# Noise_Percussion_main.net
KiCad netlist of a schematic drawn in EAGLE
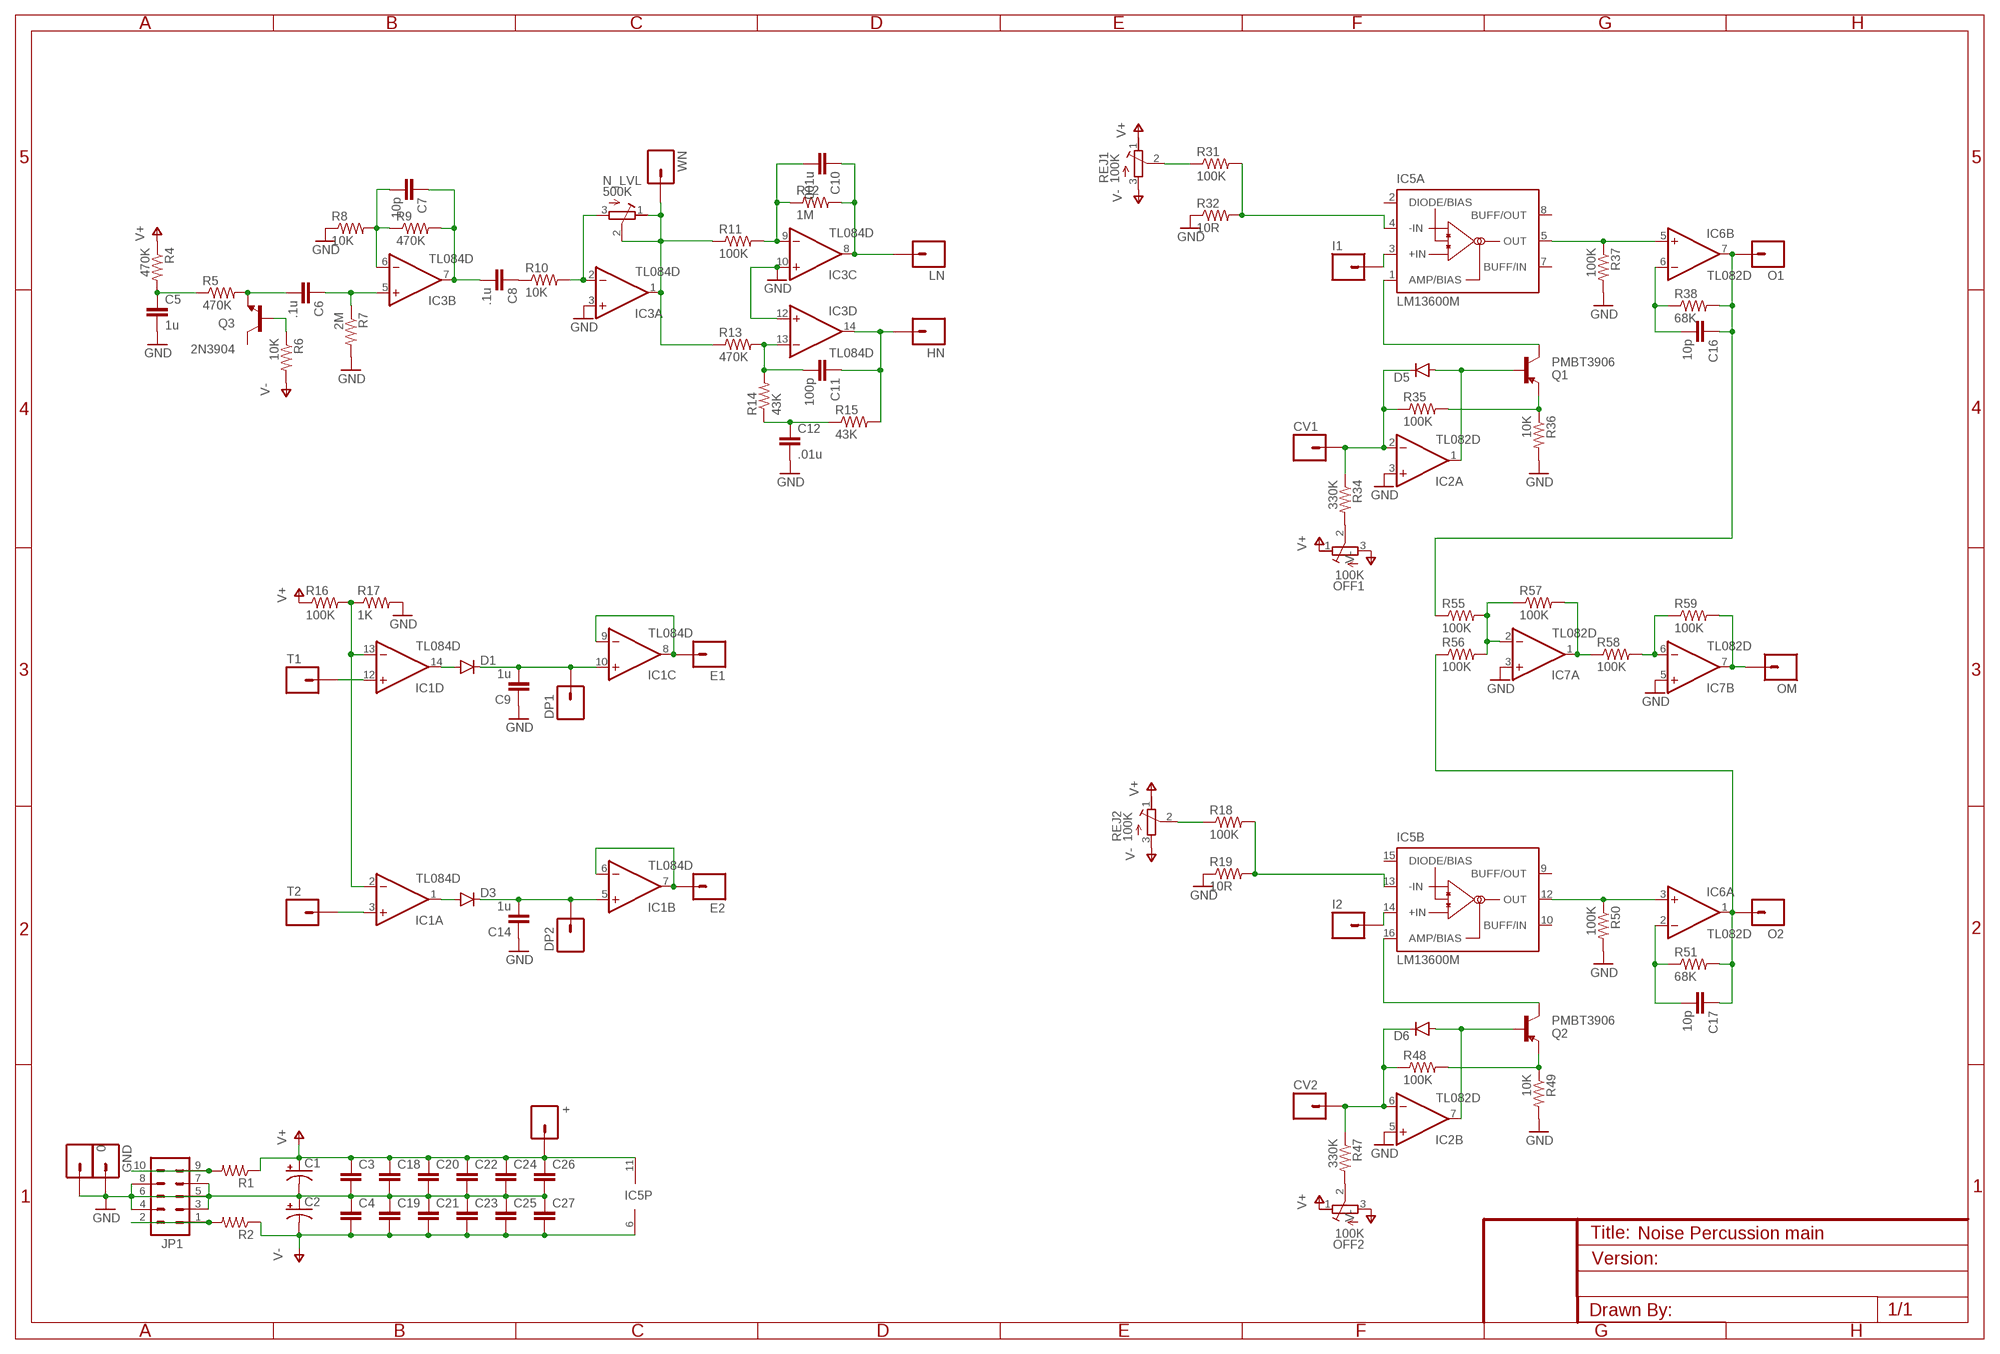
[diagram p0: schematic, sheet 1]

(export (version "E")
  (design (tool "Eeschema 10.0.6"))
  (components
    (comp (ref "+")
      (value "M01PTH")
      (footprint "eagle-import:1X01")
      (libsource (lib "eagle-import") (part "M01PTH"))
    )
    (comp (ref "0")
      (value "M01PTH")
      (footprint "eagle-import:1X01")
      (libsource (lib "eagle-import") (part "M01PTH"))
    )
    (comp (ref "C1")
      (value "CAP_POLC")
      (footprint "eagle-import:PANASONIC_C")
      (libsource (lib "eagle-import") (part "CAP_POLC"))
    )
    (comp (ref "C2")
      (value "CAP_POLC")
      (footprint "eagle-import:PANASONIC_C")
      (libsource (lib "eagle-import") (part "CAP_POLC"))
    )
    (comp (ref "C3")
      (value "CAP0805")
      (footprint "eagle-import:0805")
      (libsource (lib "eagle-import") (part "CAP0805"))
    )
    (comp (ref "C4")
      (value "CAP0805")
      (footprint "eagle-import:0805")
      (libsource (lib "eagle-import") (part "CAP0805"))
    )
    (comp (ref "C5")
      (value "1u")
      (footprint "eagle-import:0805")
      (libsource (lib "eagle-import") (part "CAP0805"))
    )
    (comp (ref "C6")
      (value ".1u")
      (footprint "eagle-import:0805")
      (libsource (lib "eagle-import") (part "CAP0805"))
    )
    (comp (ref "C7")
      (value "10p")
      (footprint "eagle-import:0805")
      (libsource (lib "eagle-import") (part "CAP0805"))
    )
    (comp (ref "C8")
      (value ".1u")
      (footprint "eagle-import:0805")
      (libsource (lib "eagle-import") (part "CAP0805"))
    )
    (comp (ref "C9")
      (value "1u")
      (footprint "eagle-import:0805")
      (libsource (lib "eagle-import") (part "CAP0805"))
    )
    (comp (ref "C10")
      (value ".001u")
      (footprint "eagle-import:0805")
      (libsource (lib "eagle-import") (part "CAP0805"))
    )
    (comp (ref "C11")
      (value "100p")
      (footprint "eagle-import:0805")
      (libsource (lib "eagle-import") (part "CAP0805"))
    )
    (comp (ref "C12")
      (value ".01u")
      (footprint "eagle-import:0805")
      (libsource (lib "eagle-import") (part "CAP0805"))
    )
    (comp (ref "C14")
      (value "1u")
      (footprint "eagle-import:0805")
      (libsource (lib "eagle-import") (part "CAP0805"))
    )
    (comp (ref "C16")
      (value "10p")
      (footprint "eagle-import:0805")
      (libsource (lib "eagle-import") (part "CAP0805"))
    )
    (comp (ref "C17")
      (value "10p")
      (footprint "eagle-import:0805")
      (libsource (lib "eagle-import") (part "CAP0805"))
    )
    (comp (ref "C18")
      (value "CAP0805")
      (footprint "eagle-import:0805")
      (libsource (lib "eagle-import") (part "CAP0805"))
    )
    (comp (ref "C19")
      (value "CAP0805")
      (footprint "eagle-import:0805")
      (libsource (lib "eagle-import") (part "CAP0805"))
    )
    (comp (ref "C20")
      (value "CAP0805")
      (footprint "eagle-import:0805")
      (libsource (lib "eagle-import") (part "CAP0805"))
    )
    (comp (ref "C21")
      (value "CAP0805")
      (footprint "eagle-import:0805")
      (libsource (lib "eagle-import") (part "CAP0805"))
    )
    (comp (ref "C22")
      (value "CAP0805")
      (footprint "eagle-import:0805")
      (libsource (lib "eagle-import") (part "CAP0805"))
    )
    (comp (ref "C23")
      (value "CAP0805")
      (footprint "eagle-import:0805")
      (libsource (lib "eagle-import") (part "CAP0805"))
    )
    (comp (ref "C24")
      (value "CAP0805")
      (footprint "eagle-import:0805")
      (libsource (lib "eagle-import") (part "CAP0805"))
    )
    (comp (ref "C25")
      (value "CAP0805")
      (footprint "eagle-import:0805")
      (libsource (lib "eagle-import") (part "CAP0805"))
    )
    (comp (ref "C26")
      (value "CAP0805")
      (footprint "eagle-import:0805")
      (libsource (lib "eagle-import") (part "CAP0805"))
    )
    (comp (ref "C27")
      (value "CAP0805")
      (footprint "eagle-import:0805")
      (libsource (lib "eagle-import") (part "CAP0805"))
    )
    (comp (ref "CV1")
      (value "M01PTH")
      (footprint "eagle-import:1X01")
      (libsource (lib "eagle-import") (part "M01PTH"))
    )
    (comp (ref "CV2")
      (value "M01PTH")
      (footprint "eagle-import:1X01")
      (libsource (lib "eagle-import") (part "M01PTH"))
    )
    (comp (ref "D1")
      (value "DIODESOD123")
      (footprint "eagle-import:SOD-123")
      (libsource (lib "eagle-import") (part "DIODESOD123"))
    )
    (comp (ref "D3")
      (value "DIODESOD123")
      (footprint "eagle-import:SOD-123")
      (libsource (lib "eagle-import") (part "DIODESOD123"))
    )
    (comp (ref "D5")
      (value "DIODESOD123")
      (footprint "eagle-import:SOD-123")
      (libsource (lib "eagle-import") (part "DIODESOD123"))
    )
    (comp (ref "D6")
      (value "DIODESOD123")
      (footprint "eagle-import:SOD-123")
      (libsource (lib "eagle-import") (part "DIODESOD123"))
    )
    (comp (ref "DP1")
      (value "M01PTH")
      (footprint "eagle-import:1X01")
      (libsource (lib "eagle-import") (part "M01PTH"))
    )
    (comp (ref "DP2")
      (value "M01PTH")
      (footprint "eagle-import:1X01")
      (libsource (lib "eagle-import") (part "M01PTH"))
    )
    (comp (ref "E1")
      (value "M01PTH")
      (footprint "eagle-import:1X01")
      (libsource (lib "eagle-import") (part "M01PTH"))
    )
    (comp (ref "E2")
      (value "M01PTH")
      (footprint "eagle-import:1X01")
      (libsource (lib "eagle-import") (part "M01PTH"))
    )
    (comp (ref "GND")
      (value "M01PTH")
      (footprint "eagle-import:1X01")
      (libsource (lib "eagle-import") (part "M01PTH"))
    )
    (comp (ref "HN")
      (value "M01PTH")
      (footprint "eagle-import:1X01")
      (libsource (lib "eagle-import") (part "M01PTH"))
    )
    (comp (ref "I1")
      (value "M01PTH")
      (footprint "eagle-import:1X01")
      (libsource (lib "eagle-import") (part "M01PTH"))
    )
    (comp (ref "I2")
      (value "M01PTH")
      (footprint "eagle-import:1X01")
      (libsource (lib "eagle-import") (part "M01PTH"))
    )
    (comp (ref "IC1")
      (value "TL084D")
      (footprint "eagle-import:SO14")
      (libsource (lib "eagle-import") (part "TL084D"))
    )
    (comp (ref "IC2")
      (value "TL082D")
      (footprint "eagle-import:SO08")
      (libsource (lib "eagle-import") (part "TL082D"))
    )
    (comp (ref "IC3")
      (value "TL084D")
      (footprint "eagle-import:SO14")
      (libsource (lib "eagle-import") (part "TL084D"))
    )
    (comp (ref "IC5")
      (value "LM13600M")
      (footprint "eagle-import:SO16")
      (libsource (lib "eagle-import") (part "LM13600M"))
    )
    (comp (ref "IC6")
      (value "TL082D")
      (footprint "eagle-import:SO08")
      (libsource (lib "eagle-import") (part "TL082D"))
    )
    (comp (ref "IC7")
      (value "TL082D")
      (footprint "eagle-import:SO08")
      (libsource (lib "eagle-import") (part "TL082D"))
    )
    (comp (ref "JP1")
      (value "M05X2PTH")
      (footprint "eagle-import:AVR_ICSP")
      (libsource (lib "eagle-import") (part "M05X2PTH"))
    )
    (comp (ref "LN")
      (value "M01PTH")
      (footprint "eagle-import:1X01")
      (libsource (lib "eagle-import") (part "M01PTH"))
    )
    (comp (ref "N_LVL")
      (value "500K")
      (footprint "eagle-import:RTRIM3314G")
      (libsource (lib "eagle-import") (part "R-TRIMM3314G"))
    )
    (comp (ref "O1")
      (value "M01PTH")
      (footprint "eagle-import:1X01")
      (libsource (lib "eagle-import") (part "M01PTH"))
    )
    (comp (ref "O2")
      (value "M01PTH")
      (footprint "eagle-import:1X01")
      (libsource (lib "eagle-import") (part "M01PTH"))
    )
    (comp (ref "OFF1")
      (value "100K")
      (footprint "eagle-import:RTRIM3314G")
      (libsource (lib "eagle-import") (part "R-TRIMM3314G"))
    )
    (comp (ref "OFF2")
      (value "100K")
      (footprint "eagle-import:RTRIM3314G")
      (libsource (lib "eagle-import") (part "R-TRIMM3314G"))
    )
    (comp (ref "OM")
      (value "M01PTH")
      (footprint "eagle-import:1X01")
      (libsource (lib "eagle-import") (part "M01PTH"))
    )
    (comp (ref "Q1")
      (value "PMBT3906")
      (footprint "eagle-import:SOT23-3")
      (libsource (lib "eagle-import") (part "TRANSISTOR_PNPPMBT3906"))
    )
    (comp (ref "Q2")
      (value "PMBT3906")
      (footprint "eagle-import:SOT23-3")
      (libsource (lib "eagle-import") (part "TRANSISTOR_PNPPMBT3906"))
    )
    (comp (ref "Q3")
      (value "2N3904")
      (footprint "eagle-import:TO92")
      (libsource (lib "eagle-import") (part "2N3904"))
    )
    (comp (ref "R1")
      (value "RESISTOR0805-RES")
      (footprint "eagle-import:0805")
      (libsource (lib "eagle-import") (part "RESISTOR0805-RES"))
    )
    (comp (ref "R2")
      (value "RESISTOR0805-RES")
      (footprint "eagle-import:0805")
      (libsource (lib "eagle-import") (part "RESISTOR0805-RES"))
    )
    (comp (ref "R4")
      (value "470K")
      (footprint "eagle-import:0805")
      (libsource (lib "eagle-import") (part "RESISTOR0805-RES"))
    )
    (comp (ref "R5")
      (value "470K")
      (footprint "eagle-import:0805")
      (libsource (lib "eagle-import") (part "RESISTOR0805-RES"))
    )
    (comp (ref "R6")
      (value "10K")
      (footprint "eagle-import:0805")
      (libsource (lib "eagle-import") (part "RESISTOR0805-RES"))
    )
    (comp (ref "R7")
      (value "2M")
      (footprint "eagle-import:0805")
      (libsource (lib "eagle-import") (part "RESISTOR0805-RES"))
    )
    (comp (ref "R8")
      (value "10K")
      (footprint "eagle-import:0805")
      (libsource (lib "eagle-import") (part "RESISTOR0805-RES"))
    )
    (comp (ref "R9")
      (value "470K")
      (footprint "eagle-import:0805")
      (libsource (lib "eagle-import") (part "RESISTOR0805-RES"))
    )
    (comp (ref "R10")
      (value "10K")
      (footprint "eagle-import:0805")
      (libsource (lib "eagle-import") (part "RESISTOR0805-RES"))
    )
    (comp (ref "R11")
      (value "100K")
      (footprint "eagle-import:0805")
      (libsource (lib "eagle-import") (part "RESISTOR0805-RES"))
    )
    (comp (ref "R12")
      (value "1M")
      (footprint "eagle-import:0805")
      (libsource (lib "eagle-import") (part "RESISTOR0805-RES"))
    )
    (comp (ref "R13")
      (value "470K")
      (footprint "eagle-import:0805")
      (libsource (lib "eagle-import") (part "RESISTOR0805-RES"))
    )
    (comp (ref "R14")
      (value "43K")
      (footprint "eagle-import:0805")
      (libsource (lib "eagle-import") (part "RESISTOR0805-RES"))
    )
    (comp (ref "R15")
      (value "43K")
      (footprint "eagle-import:0805")
      (libsource (lib "eagle-import") (part "RESISTOR0805-RES"))
    )
    (comp (ref "R16")
      (value "100K")
      (footprint "eagle-import:0805")
      (libsource (lib "eagle-import") (part "RESISTOR0805-RES"))
    )
    (comp (ref "R17")
      (value "1K")
      (footprint "eagle-import:0805")
      (libsource (lib "eagle-import") (part "RESISTOR0805-RES"))
    )
    (comp (ref "R18")
      (value "100K")
      (footprint "eagle-import:0805")
      (libsource (lib "eagle-import") (part "RESISTOR0805-RES"))
    )
    (comp (ref "R19")
      (value "10R")
      (footprint "eagle-import:0805")
      (libsource (lib "eagle-import") (part "RESISTOR0805-RES"))
    )
    (comp (ref "R31")
      (value "100K")
      (footprint "eagle-import:0805")
      (libsource (lib "eagle-import") (part "RESISTOR0805-RES"))
    )
    (comp (ref "R32")
      (value "10R")
      (footprint "eagle-import:0805")
      (libsource (lib "eagle-import") (part "RESISTOR0805-RES"))
    )
    (comp (ref "R34")
      (value "330K")
      (footprint "eagle-import:0805")
      (libsource (lib "eagle-import") (part "RESISTOR0805-RES"))
    )
    (comp (ref "R35")
      (value "100K")
      (footprint "eagle-import:0805")
      (libsource (lib "eagle-import") (part "RESISTOR0805-RES"))
    )
    (comp (ref "R36")
      (value "10K")
      (footprint "eagle-import:0805")
      (libsource (lib "eagle-import") (part "RESISTOR0805-RES"))
    )
    (comp (ref "R37")
      (value "100K")
      (footprint "eagle-import:0805")
      (libsource (lib "eagle-import") (part "RESISTOR0805-RES"))
    )
    (comp (ref "R38")
      (value "68K")
      (footprint "eagle-import:0805")
      (libsource (lib "eagle-import") (part "RESISTOR0805-RES"))
    )
    (comp (ref "R47")
      (value "330K")
      (footprint "eagle-import:0805")
      (libsource (lib "eagle-import") (part "RESISTOR0805-RES"))
    )
    (comp (ref "R48")
      (value "100K")
      (footprint "eagle-import:0805")
      (libsource (lib "eagle-import") (part "RESISTOR0805-RES"))
    )
    (comp (ref "R49")
      (value "10K")
      (footprint "eagle-import:0805")
      (libsource (lib "eagle-import") (part "RESISTOR0805-RES"))
    )
    (comp (ref "R50")
      (value "100K")
      (footprint "eagle-import:0805")
      (libsource (lib "eagle-import") (part "RESISTOR0805-RES"))
    )
    (comp (ref "R51")
      (value "68K")
      (footprint "eagle-import:0805")
      (libsource (lib "eagle-import") (part "RESISTOR0805-RES"))
    )
    (comp (ref "R55")
      (value "100K")
      (footprint "eagle-import:0805")
      (libsource (lib "eagle-import") (part "RESISTOR0805-RES"))
    )
    (comp (ref "R56")
      (value "100K")
      (footprint "eagle-import:0805")
      (libsource (lib "eagle-import") (part "RESISTOR0805-RES"))
    )
    (comp (ref "R57")
      (value "100K")
      (footprint "eagle-import:0805")
      (libsource (lib "eagle-import") (part "RESISTOR0805-RES"))
    )
    (comp (ref "R58")
      (value "100K")
      (footprint "eagle-import:0805")
      (libsource (lib "eagle-import") (part "RESISTOR0805-RES"))
    )
    (comp (ref "R59")
      (value "100K")
      (footprint "eagle-import:0805")
      (libsource (lib "eagle-import") (part "RESISTOR0805-RES"))
    )
    (comp (ref "REJ1")
      (value "100K")
      (footprint "eagle-import:RTRIM3314G")
      (libsource (lib "eagle-import") (part "R-TRIMM3314G"))
    )
    (comp (ref "REJ2")
      (value "100K")
      (footprint "eagle-import:RTRIM3314G")
      (libsource (lib "eagle-import") (part "R-TRIMM3314G"))
    )
    (comp (ref "T1")
      (value "M01PTH")
      (footprint "eagle-import:1X01")
      (libsource (lib "eagle-import") (part "M01PTH"))
    )
    (comp (ref "T2")
      (value "M01PTH")
      (footprint "eagle-import:1X01")
      (libsource (lib "eagle-import") (part "M01PTH"))
    )
    (comp (ref "WN")
      (value "M01PTH")
      (footprint "eagle-import:1X01")
      (libsource (lib "eagle-import") (part "M01PTH"))
    )
  )
  (nets
    (net (code "1") (name "GND") (class "Default")
      (node (ref "0") (pin "1") (pinfunction "1_1") (pintype "passive"))
      (node (ref "C1") (pin "-") (pinfunction "-_-") (pintype "passive"))
      (node (ref "C12") (pin "2") (pinfunction "2_2") (pintype "passive"))
      (node (ref "C14") (pin "1") (pinfunction "1_1") (pintype "passive"))
      (node (ref "C18") (pin "2") (pinfunction "2_2") (pintype "passive"))
      (node (ref "C19") (pin "1") (pinfunction "1_1") (pintype "passive"))
      (node (ref "C2") (pin "+") (pinfunction "+_+") (pintype "passive"))
      (node (ref "C20") (pin "2") (pinfunction "2_2") (pintype "passive"))
      (node (ref "C21") (pin "1") (pinfunction "1_1") (pintype "passive"))
      (node (ref "C22") (pin "2") (pinfunction "2_2") (pintype "passive"))
      (node (ref "C23") (pin "1") (pinfunction "1_1") (pintype "passive"))
      (node (ref "C24") (pin "2") (pinfunction "2_2") (pintype "passive"))
      (node (ref "C25") (pin "1") (pinfunction "1_1") (pintype "passive"))
      (node (ref "C26") (pin "2") (pinfunction "2_2") (pintype "passive"))
      (node (ref "C27") (pin "1") (pinfunction "1_1") (pintype "passive"))
      (node (ref "C3") (pin "2") (pinfunction "2_2") (pintype "passive"))
      (node (ref "C4") (pin "1") (pinfunction "1_1") (pintype "passive"))
      (node (ref "C5") (pin "2") (pinfunction "2_2") (pintype "passive"))
      (node (ref "C9") (pin "1") (pinfunction "1_1") (pintype "passive"))
      (node (ref "GND") (pin "1") (pinfunction "1_1") (pintype "passive"))
      (node (ref "IC2") (pin "3") (pinfunction "+IN_3") (pintype "input"))
      (node (ref "IC2") (pin "5") (pinfunction "+IN_5") (pintype "input"))
      (node (ref "IC3") (pin "10") (pinfunction "+IN_10") (pintype "input"))
      (node (ref "IC3") (pin "12") (pinfunction "+IN_12") (pintype "input"))
      (node (ref "IC3") (pin "3") (pinfunction "+IN_3") (pintype "input"))
      (node (ref "IC7") (pin "3") (pinfunction "+IN_3") (pintype "input"))
      (node (ref "IC7") (pin "5") (pinfunction "+IN_5") (pintype "input"))
      (node (ref "JP1") (pin "3") (pinfunction "3_3") (pintype "passive"))
      (node (ref "JP1") (pin "4") (pinfunction "4_4") (pintype "passive"))
      (node (ref "JP1") (pin "5") (pinfunction "5_5") (pintype "passive"))
      (node (ref "JP1") (pin "6") (pinfunction "6_6") (pintype "passive"))
      (node (ref "JP1") (pin "7") (pinfunction "7_7") (pintype "passive"))
      (node (ref "JP1") (pin "8") (pinfunction "8_8") (pintype "passive"))
      (node (ref "R17") (pin "2") (pinfunction "2_2") (pintype "passive"))
      (node (ref "R19") (pin "1") (pinfunction "1_1") (pintype "passive"))
      (node (ref "R32") (pin "1") (pinfunction "1_1") (pintype "passive"))
      (node (ref "R36") (pin "2") (pinfunction "2_2") (pintype "passive"))
      (node (ref "R37") (pin "2") (pinfunction "2_2") (pintype "passive"))
      (node (ref "R49") (pin "2") (pinfunction "2_2") (pintype "passive"))
      (node (ref "R50") (pin "2") (pinfunction "2_2") (pintype "passive"))
      (node (ref "R7") (pin "2") (pinfunction "2_2") (pintype "passive"))
      (node (ref "R8") (pin "1") (pinfunction "1_1") (pintype "passive"))
    )
    (net (code "2") (name "Net-(C5-Pad1)") (class "Default")
      (node (ref "C5") (pin "1") (pinfunction "1_1") (pintype "passive"))
      (node (ref "R4") (pin "2") (pinfunction "2_2") (pintype "passive"))
      (node (ref "R5") (pin "1") (pinfunction "1_1") (pintype "passive"))
    )
    (net (code "3") (name "Net-(C8-Pad1)") (class "Default")
      (node (ref "C8") (pin "1") (pinfunction "1_1") (pintype "passive"))
      (node (ref "R10") (pin "1") (pinfunction "1_1") (pintype "passive"))
    )
    (net (code "4") (name "Net-(C12-Pad1)") (class "Default")
      (node (ref "C12") (pin "1") (pinfunction "1_1") (pintype "passive"))
      (node (ref "R14") (pin "1") (pinfunction "1_1") (pintype "passive"))
      (node (ref "R15") (pin "1") (pinfunction "1_1") (pintype "passive"))
    )
    (net (code "5") (name "Net-(IC1A-+IN)") (class "Default")
      (node (ref "IC1") (pin "3") (pinfunction "+IN_3") (pintype "input"))
      (node (ref "T2") (pin "1") (pinfunction "1_1") (pintype "passive"))
    )
    (net (code "6") (name "Net-(IC1A--IN)") (class "Default")
      (node (ref "IC1") (pin "13") (pinfunction "-IN_13") (pintype "input"))
      (node (ref "IC1") (pin "2") (pinfunction "-IN_2") (pintype "input"))
      (node (ref "R16") (pin "2") (pinfunction "2_2") (pintype "passive"))
      (node (ref "R17") (pin "1") (pinfunction "1_1") (pintype "passive"))
    )
    (net (code "7") (name "Net-(IC1A-OUT)") (class "Default")
      (node (ref "D3") (pin "A") (pinfunction "A_A") (pintype "passive"))
      (node (ref "IC1") (pin "1") (pinfunction "OUT_1") (pintype "output"))
    )
    (net (code "8") (name "Net-(IC1B-+IN)") (class "Default")
      (node (ref "C14") (pin "2") (pinfunction "2_2") (pintype "passive"))
      (node (ref "D3") (pin "C") (pinfunction "C_C") (pintype "passive"))
      (node (ref "DP2") (pin "1") (pinfunction "1_1") (pintype "passive"))
      (node (ref "IC1") (pin "5") (pinfunction "+IN_5") (pintype "input"))
    )
    (net (code "9") (name "Net-(IC1B--IN)") (class "Default")
      (node (ref "E2") (pin "1") (pinfunction "1_1") (pintype "passive"))
      (node (ref "IC1") (pin "6") (pinfunction "-IN_6") (pintype "input"))
      (node (ref "IC1") (pin "7") (pinfunction "OUT_7") (pintype "output"))
    )
    (net (code "10") (name "Net-(IC1C-+IN)") (class "Default")
      (node (ref "C9") (pin "2") (pinfunction "2_2") (pintype "passive"))
      (node (ref "D1") (pin "C") (pinfunction "C_C") (pintype "passive"))
      (node (ref "DP1") (pin "1") (pinfunction "1_1") (pintype "passive"))
      (node (ref "IC1") (pin "10") (pinfunction "+IN_10") (pintype "input"))
    )
    (net (code "11") (name "Net-(IC1C--IN)") (class "Default")
      (node (ref "E1") (pin "1") (pinfunction "1_1") (pintype "passive"))
      (node (ref "IC1") (pin "8") (pinfunction "OUT_8") (pintype "output"))
      (node (ref "IC1") (pin "9") (pinfunction "-IN_9") (pintype "input"))
    )
    (net (code "12") (name "Net-(IC1D-+IN)") (class "Default")
      (node (ref "IC1") (pin "12") (pinfunction "+IN_12") (pintype "input"))
      (node (ref "T1") (pin "1") (pinfunction "1_1") (pintype "passive"))
    )
    (net (code "13") (name "Net-(IC1D-OUT)") (class "Default")
      (node (ref "D1") (pin "A") (pinfunction "A_A") (pintype "passive"))
      (node (ref "IC1") (pin "14") (pinfunction "OUT_14") (pintype "output"))
    )
    (net (code "14") (name "Net-(IC2A--IN)") (class "Default")
      (node (ref "CV1") (pin "1") (pinfunction "1_1") (pintype "passive"))
      (node (ref "D5") (pin "C") (pinfunction "C_C") (pintype "passive"))
      (node (ref "IC2") (pin "2") (pinfunction "-IN_2") (pintype "input"))
      (node (ref "R34") (pin "1") (pinfunction "1_1") (pintype "passive"))
      (node (ref "R35") (pin "1") (pinfunction "1_1") (pintype "passive"))
    )
    (net (code "15") (name "Net-(IC2A-OUT)") (class "Default")
      (node (ref "D5") (pin "A") (pinfunction "A_A") (pintype "passive"))
      (node (ref "IC2") (pin "1") (pinfunction "OUT_1") (pintype "output"))
      (node (ref "Q1") (pin "1") (pinfunction "B_1") (pintype "passive"))
    )
    (net (code "16") (name "Net-(IC2B--IN)") (class "Default")
      (node (ref "CV2") (pin "1") (pinfunction "1_1") (pintype "passive"))
      (node (ref "D6") (pin "C") (pinfunction "C_C") (pintype "passive"))
      (node (ref "IC2") (pin "6") (pinfunction "-IN_6") (pintype "input"))
      (node (ref "R47") (pin "1") (pinfunction "1_1") (pintype "passive"))
      (node (ref "R48") (pin "1") (pinfunction "1_1") (pintype "passive"))
    )
    (net (code "17") (name "Net-(IC2B-OUT)") (class "Default")
      (node (ref "D6") (pin "A") (pinfunction "A_A") (pintype "passive"))
      (node (ref "IC2") (pin "7") (pinfunction "OUT_7") (pintype "output"))
      (node (ref "Q2") (pin "1") (pinfunction "B_1") (pintype "passive"))
    )
    (net (code "18") (name "Net-(IC3A--IN)") (class "Default")
      (node (ref "IC3") (pin "2") (pinfunction "-IN_2") (pintype "input"))
      (node (ref "N_LVL") (pin "3") (pinfunction "A_3") (pintype "passive"))
      (node (ref "R10") (pin "2") (pinfunction "2_2") (pintype "passive"))
    )
    (net (code "19") (name "Net-(IC3A-OUT)") (class "Default")
      (node (ref "IC3") (pin "1") (pinfunction "OUT_1") (pintype "output"))
      (node (ref "N_LVL") (pin "1") (pinfunction "E_1") (pintype "passive"))
      (node (ref "N_LVL") (pin "2") (pinfunction "S_2") (pintype "passive"))
      (node (ref "R11") (pin "1") (pinfunction "1_1") (pintype "passive"))
      (node (ref "R13") (pin "1") (pinfunction "1_1") (pintype "passive"))
      (node (ref "WN") (pin "1") (pinfunction "1_1") (pintype "passive"))
    )
    (net (code "20") (name "Net-(IC3B-+IN)") (class "Default")
      (node (ref "C6") (pin "1") (pinfunction "1_1") (pintype "passive"))
      (node (ref "IC3") (pin "5") (pinfunction "+IN_5") (pintype "input"))
      (node (ref "R7") (pin "1") (pinfunction "1_1") (pintype "passive"))
    )
    (net (code "21") (name "Net-(IC3B--IN)") (class "Default")
      (node (ref "C7") (pin "2") (pinfunction "2_2") (pintype "passive"))
      (node (ref "IC3") (pin "6") (pinfunction "-IN_6") (pintype "input"))
      (node (ref "R8") (pin "2") (pinfunction "2_2") (pintype "passive"))
      (node (ref "R9") (pin "1") (pinfunction "1_1") (pintype "passive"))
    )
    (net (code "22") (name "Net-(IC3B-OUT)") (class "Default")
      (node (ref "C7") (pin "1") (pinfunction "1_1") (pintype "passive"))
      (node (ref "C8") (pin "2") (pinfunction "2_2") (pintype "passive"))
      (node (ref "IC3") (pin "7") (pinfunction "OUT_7") (pintype "output"))
      (node (ref "R9") (pin "2") (pinfunction "2_2") (pintype "passive"))
    )
    (net (code "23") (name "Net-(IC3C--IN)") (class "Default")
      (node (ref "C10") (pin "2") (pinfunction "2_2") (pintype "passive"))
      (node (ref "IC3") (pin "9") (pinfunction "-IN_9") (pintype "input"))
      (node (ref "R11") (pin "2") (pinfunction "2_2") (pintype "passive"))
      (node (ref "R12") (pin "1") (pinfunction "1_1") (pintype "passive"))
    )
    (net (code "24") (name "Net-(IC3C-OUT)") (class "Default")
      (node (ref "C10") (pin "1") (pinfunction "1_1") (pintype "passive"))
      (node (ref "IC3") (pin "8") (pinfunction "OUT_8") (pintype "output"))
      (node (ref "LN") (pin "1") (pinfunction "1_1") (pintype "passive"))
      (node (ref "R12") (pin "2") (pinfunction "2_2") (pintype "passive"))
    )
    (net (code "25") (name "Net-(IC3D--IN)") (class "Default")
      (node (ref "C11") (pin "2") (pinfunction "2_2") (pintype "passive"))
      (node (ref "IC3") (pin "13") (pinfunction "-IN_13") (pintype "input"))
      (node (ref "R13") (pin "2") (pinfunction "2_2") (pintype "passive"))
      (node (ref "R14") (pin "2") (pinfunction "2_2") (pintype "passive"))
    )
    (net (code "26") (name "Net-(IC3D-OUT)") (class "Default")
      (node (ref "C11") (pin "1") (pinfunction "1_1") (pintype "passive"))
      (node (ref "HN") (pin "1") (pinfunction "1_1") (pintype "passive"))
      (node (ref "IC3") (pin "14") (pinfunction "OUT_14") (pintype "output"))
      (node (ref "R15") (pin "2") (pinfunction "2_2") (pintype "passive"))
    )
    (net (code "27") (name "Net-(IC5A-+IN)") (class "Default")
      (node (ref "I1") (pin "1") (pinfunction "1_1") (pintype "passive"))
      (node (ref "IC5") (pin "3") (pinfunction "+IN_3") (pintype "input"))
    )
    (net (code "28") (name "Net-(IC5A--IN)") (class "Default")
      (node (ref "IC5") (pin "4") (pinfunction "-IN_4") (pintype "input"))
      (node (ref "R31") (pin "2") (pinfunction "2_2") (pintype "passive"))
      (node (ref "R32") (pin "2") (pinfunction "2_2") (pintype "passive"))
    )
    (net (code "29") (name "Net-(IC5A-AMP{slash}BIAS)") (class "Default")
      (node (ref "IC5") (pin "1") (pinfunction "AMP/BIAS_1") (pintype "passive"))
      (node (ref "Q1") (pin "3") (pinfunction "C_3") (pintype "passive"))
    )
    (net (code "30") (name "Net-(IC5A-OUT)") (class "Default")
      (node (ref "IC5") (pin "5") (pinfunction "OUT_5") (pintype "output"))
      (node (ref "IC6") (pin "5") (pinfunction "+IN_5") (pintype "input"))
      (node (ref "R37") (pin "1") (pinfunction "1_1") (pintype "passive"))
    )
    (net (code "31") (name "Net-(IC5B-+IN)") (class "Default")
      (node (ref "I2") (pin "1") (pinfunction "1_1") (pintype "passive"))
      (node (ref "IC5") (pin "14") (pinfunction "+IN_14") (pintype "input"))
    )
    (net (code "32") (name "Net-(IC5B--IN)") (class "Default")
      (node (ref "IC5") (pin "13") (pinfunction "-IN_13") (pintype "input"))
      (node (ref "R18") (pin "2") (pinfunction "2_2") (pintype "passive"))
      (node (ref "R19") (pin "2") (pinfunction "2_2") (pintype "passive"))
    )
    (net (code "33") (name "Net-(IC5B-AMP{slash}BIAS)") (class "Default")
      (node (ref "IC5") (pin "16") (pinfunction "AMP/BIAS_16") (pintype "passive"))
      (node (ref "Q2") (pin "3") (pinfunction "C_3") (pintype "passive"))
    )
    (net (code "34") (name "Net-(IC5B-OUT)") (class "Default")
      (node (ref "IC5") (pin "12") (pinfunction "OUT_12") (pintype "output"))
      (node (ref "IC6") (pin "3") (pinfunction "+IN_3") (pintype "input"))
      (node (ref "R50") (pin "1") (pinfunction "1_1") (pintype "passive"))
    )
    (net (code "35") (name "Net-(IC6A--IN)") (class "Default")
      (node (ref "C17") (pin "2") (pinfunction "2_2") (pintype "passive"))
      (node (ref "IC6") (pin "2") (pinfunction "-IN_2") (pintype "input"))
      (node (ref "R51") (pin "1") (pinfunction "1_1") (pintype "passive"))
    )
    (net (code "36") (name "Net-(IC6A-OUT)") (class "Default")
      (node (ref "C17") (pin "1") (pinfunction "1_1") (pintype "passive"))
      (node (ref "IC6") (pin "1") (pinfunction "OUT_1") (pintype "output"))
      (node (ref "O2") (pin "1") (pinfunction "1_1") (pintype "passive"))
      (node (ref "R51") (pin "2") (pinfunction "2_2") (pintype "passive"))
      (node (ref "R56") (pin "1") (pinfunction "1_1") (pintype "passive"))
    )
    (net (code "37") (name "Net-(IC6B--IN)") (class "Default")
      (node (ref "C16") (pin "2") (pinfunction "2_2") (pintype "passive"))
      (node (ref "IC6") (pin "6") (pinfunction "-IN_6") (pintype "input"))
      (node (ref "R38") (pin "1") (pinfunction "1_1") (pintype "passive"))
    )
    (net (code "38") (name "Net-(IC6B-OUT)") (class "Default")
      (node (ref "C16") (pin "1") (pinfunction "1_1") (pintype "passive"))
      (node (ref "IC6") (pin "7") (pinfunction "OUT_7") (pintype "output"))
      (node (ref "O1") (pin "1") (pinfunction "1_1") (pintype "passive"))
      (node (ref "R38") (pin "2") (pinfunction "2_2") (pintype "passive"))
      (node (ref "R55") (pin "1") (pinfunction "1_1") (pintype "passive"))
    )
    (net (code "39") (name "Net-(IC7A--IN)") (class "Default")
      (node (ref "IC7") (pin "2") (pinfunction "-IN_2") (pintype "input"))
      (node (ref "R55") (pin "2") (pinfunction "2_2") (pintype "passive"))
      (node (ref "R56") (pin "2") (pinfunction "2_2") (pintype "passive"))
      (node (ref "R57") (pin "1") (pinfunction "1_1") (pintype "passive"))
    )
    (net (code "40") (name "Net-(IC7A-OUT)") (class "Default")
      (node (ref "IC7") (pin "1") (pinfunction "OUT_1") (pintype "output"))
      (node (ref "R57") (pin "2") (pinfunction "2_2") (pintype "passive"))
      (node (ref "R58") (pin "1") (pinfunction "1_1") (pintype "passive"))
    )
    (net (code "41") (name "Net-(IC7B--IN)") (class "Default")
      (node (ref "IC7") (pin "6") (pinfunction "-IN_6") (pintype "input"))
      (node (ref "R58") (pin "2") (pinfunction "2_2") (pintype "passive"))
      (node (ref "R59") (pin "1") (pinfunction "1_1") (pintype "passive"))
    )
    (net (code "42") (name "Net-(IC7B-OUT)") (class "Default")
      (node (ref "IC7") (pin "7") (pinfunction "OUT_7") (pintype "output"))
      (node (ref "OM") (pin "1") (pinfunction "1_1") (pintype "passive"))
      (node (ref "R59") (pin "2") (pinfunction "2_2") (pintype "passive"))
    )
    (net (code "43") (name "Net-(JP1-Pad1)") (class "Default")
      (node (ref "JP1") (pin "1") (pinfunction "1_1") (pintype "passive"))
      (node (ref "JP1") (pin "2") (pinfunction "2_2") (pintype "passive"))
      (node (ref "R2") (pin "2") (pinfunction "2_2") (pintype "passive"))
    )
    (net (code "44") (name "Net-(JP1-Pad10)") (class "Default")
      (node (ref "JP1") (pin "10") (pinfunction "10_10") (pintype "passive"))
      (node (ref "JP1") (pin "9") (pinfunction "9_9") (pintype "passive"))
      (node (ref "R1") (pin "2") (pinfunction "2_2") (pintype "passive"))
    )
    (net (code "45") (name "Net-(OFF1-S)") (class "Default")
      (node (ref "OFF1") (pin "2") (pinfunction "S_2") (pintype "passive"))
      (node (ref "R34") (pin "2") (pinfunction "2_2") (pintype "passive"))
    )
    (net (code "46") (name "Net-(OFF2-S)") (class "Default")
      (node (ref "OFF2") (pin "2") (pinfunction "S_2") (pintype "passive"))
      (node (ref "R47") (pin "2") (pinfunction "2_2") (pintype "passive"))
    )
    (net (code "47") (name "Net-(Q1-E)") (class "Default")
      (node (ref "Q1") (pin "2") (pinfunction "E_2") (pintype "passive"))
      (node (ref "R35") (pin "2") (pinfunction "2_2") (pintype "passive"))
      (node (ref "R36") (pin "1") (pinfunction "1_1") (pintype "passive"))
    )
    (net (code "48") (name "Net-(Q2-E)") (class "Default")
      (node (ref "Q2") (pin "2") (pinfunction "E_2") (pintype "passive"))
      (node (ref "R48") (pin "2") (pinfunction "2_2") (pintype "passive"))
      (node (ref "R49") (pin "1") (pinfunction "1_1") (pintype "passive"))
    )
    (net (code "49") (name "Net-(Q3-B)") (class "Default")
      (node (ref "Q3") (pin "2") (pinfunction "B_2") (pintype "passive"))
      (node (ref "R6") (pin "1") (pinfunction "1_1") (pintype "passive"))
    )
    (net (code "50") (name "Net-(Q3-E)") (class "Default")
      (node (ref "C6") (pin "2") (pinfunction "2_2") (pintype "passive"))
      (node (ref "Q3") (pin "3") (pinfunction "E_3") (pintype "passive"))
      (node (ref "R5") (pin "2") (pinfunction "2_2") (pintype "passive"))
    )
    (net (code "51") (name "Net-(REJ1-S)") (class "Default")
      (node (ref "R31") (pin "1") (pinfunction "1_1") (pintype "passive"))
      (node (ref "REJ1") (pin "2") (pinfunction "S_2") (pintype "passive"))
    )
    (net (code "52") (name "Net-(REJ2-S)") (class "Default")
      (node (ref "R18") (pin "1") (pinfunction "1_1") (pintype "passive"))
      (node (ref "REJ2") (pin "2") (pinfunction "S_2") (pintype "passive"))
    )
    (net (code "53") (name "V+") (class "Default")
      (node (ref "+") (pin "1") (pinfunction "1_1") (pintype "passive"))
      (node (ref "C1") (pin "+") (pinfunction "+_+") (pintype "passive"))
      (node (ref "C18") (pin "1") (pinfunction "1_1") (pintype "passive"))
      (node (ref "C20") (pin "1") (pinfunction "1_1") (pintype "passive"))
      (node (ref "C22") (pin "1") (pinfunction "1_1") (pintype "passive"))
      (node (ref "C24") (pin "1") (pinfunction "1_1") (pintype "passive"))
      (node (ref "C26") (pin "1") (pinfunction "1_1") (pintype "passive"))
      (node (ref "C3") (pin "1") (pinfunction "1_1") (pintype "passive"))
      (node (ref "IC5") (pin "11") (pinfunction "V+_11") (pintype "power_in"))
      (node (ref "OFF1") (pin "1") (pinfunction "E_1") (pintype "passive"))
      (node (ref "OFF2") (pin "1") (pinfunction "E_1") (pintype "passive"))
      (node (ref "R1") (pin "1") (pinfunction "1_1") (pintype "passive"))
      (node (ref "R16") (pin "1") (pinfunction "1_1") (pintype "passive"))
      (node (ref "R4") (pin "1") (pinfunction "1_1") (pintype "passive"))
      (node (ref "REJ1") (pin "1") (pinfunction "E_1") (pintype "passive"))
      (node (ref "REJ2") (pin "1") (pinfunction "E_1") (pintype "passive"))
    )
    (net (code "54") (name "V-") (class "Default")
      (node (ref "C19") (pin "2") (pinfunction "2_2") (pintype "passive"))
      (node (ref "C2") (pin "-") (pinfunction "-_-") (pintype "passive"))
      (node (ref "C21") (pin "2") (pinfunction "2_2") (pintype "passive"))
      (node (ref "C23") (pin "2") (pinfunction "2_2") (pintype "passive"))
      (node (ref "C25") (pin "2") (pinfunction "2_2") (pintype "passive"))
      (node (ref "C27") (pin "2") (pinfunction "2_2") (pintype "passive"))
      (node (ref "C4") (pin "2") (pinfunction "2_2") (pintype "passive"))
      (node (ref "IC5") (pin "6") (pinfunction "V-_6") (pintype "power_in"))
      (node (ref "OFF1") (pin "3") (pinfunction "A_3") (pintype "passive"))
      (node (ref "OFF2") (pin "3") (pinfunction "A_3") (pintype "passive"))
      (node (ref "R2") (pin "1") (pinfunction "1_1") (pintype "passive"))
      (node (ref "R6") (pin "2") (pinfunction "2_2") (pintype "passive"))
      (node (ref "REJ1") (pin "3") (pinfunction "A_3") (pintype "passive"))
      (node (ref "REJ2") (pin "3") (pinfunction "A_3") (pintype "passive"))
    )
    (net (code "55") (name "unconnected-(IC5A-BUFF{slash}IN-Pad7)") (class "Default")
      (node (ref "IC5") (pin "7") (pinfunction "BUFF/IN_7") (pintype "input"))
    )
    (net (code "56") (name "unconnected-(IC5A-BUFF{slash}OUT-Pad8)") (class "Default")
      (node (ref "IC5") (pin "8") (pinfunction "BUFF/OUT_8") (pintype "output"))
    )
    (net (code "57") (name "unconnected-(IC5A-DIODE{slash}BIAS-Pad2)") (class "Default")
      (node (ref "IC5") (pin "2") (pinfunction "DIODE/BIAS_2") (pintype "passive"))
    )
    (net (code "58") (name "unconnected-(IC5B-BUFF{slash}IN-Pad10)") (class "Default")
      (node (ref "IC5") (pin "10") (pinfunction "BUFF/IN_10") (pintype "input"))
    )
    (net (code "59") (name "unconnected-(IC5B-BUFF{slash}OUT-Pad9)") (class "Default")
      (node (ref "IC5") (pin "9") (pinfunction "BUFF/OUT_9") (pintype "output"))
    )
    (net (code "60") (name "unconnected-(IC5B-DIODE{slash}BIAS-Pad15)") (class "Default")
      (node (ref "IC5") (pin "15") (pinfunction "DIODE/BIAS_15") (pintype "passive"))
    )
    (net (code "61") (name "unconnected-(Q3-C-Pad1)") (class "Default")
      (node (ref "Q3") (pin "1") (pinfunction "C_1") (pintype "passive"))
    )
  )
)
